# QuadSPIFlash.net
KiCad netlist of a schematic drawn in Altium Designer
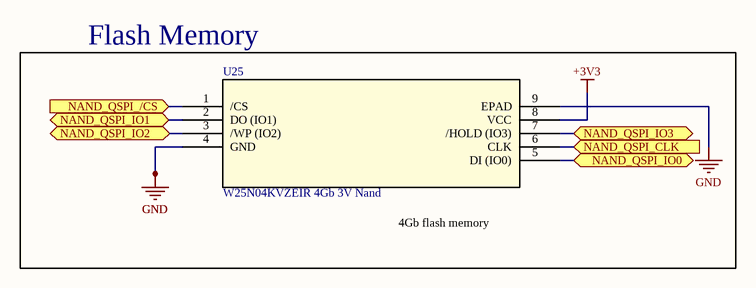
[diagram p0: QuadSPIFlash.SchDoc]

(export (version "E")
  (design (tool "Eeschema 10.0.6"))
  (components
    (comp (ref "U25")
      (value "W25N04KVZEIR 4Gb 3V Nand")
      (footprint "W25N04KVZEIR 4Gb 3V Nand-Footprint-1")
      (description "4G-BIT Serial Nand Flash, 3V")
      (libsource (lib "University of Calgary - SOAR") (part "W25N04KVZEIR 4Gb 3V Nand-Symbol-1"))
    )
  )
  (nets
    (net (code "1") (name "+3V3") (class "Default")
      (node (ref "U25") (pin "8") (pinfunction "VCC_8") (pintype "power_in"))
    )
    (net (code "2") (name "/NAND_QSPI_CLK") (class "Default")
      (node (ref "U25") (pin "6") (pinfunction "CLK_6") (pintype "passive"))
    )
    (net (code "3") (name "/NAND_QSPI_IO0") (class "Default")
      (node (ref "U25") (pin "5") (pinfunction "DI_(IO0)_5") (pintype "passive"))
    )
    (net (code "4") (name "/NAND_QSPI_IO1") (class "Default")
      (node (ref "U25") (pin "2") (pinfunction "DO_(IO1)_2") (pintype "passive"))
    )
    (net (code "5") (name "/NAND_QSPI_IO2") (class "Default")
      (node (ref "U25") (pin "3") (pinfunction "/WP_(IO2)_3") (pintype "passive"))
    )
    (net (code "6") (name "/NAND_QSPI_IO3") (class "Default")
      (node (ref "U25") (pin "7") (pinfunction "/HOLD_(IO3)_7") (pintype "passive"))
    )
    (net (code "7") (name "/NAND_QSPI_{slash}CS") (class "Default")
      (node (ref "U25") (pin "1") (pinfunction "/CS_1") (pintype "passive"))
    )
    (net (code "8") (name "GND") (class "Default")
      (node (ref "U25") (pin "4") (pinfunction "GND_4") (pintype "power_in"))
      (node (ref "U25") (pin "9") (pinfunction "EPAD_9") (pintype "passive"))
    )
  )
)
